# ice40.net
KiCad netlist of a schematic drawn in Altium Designer
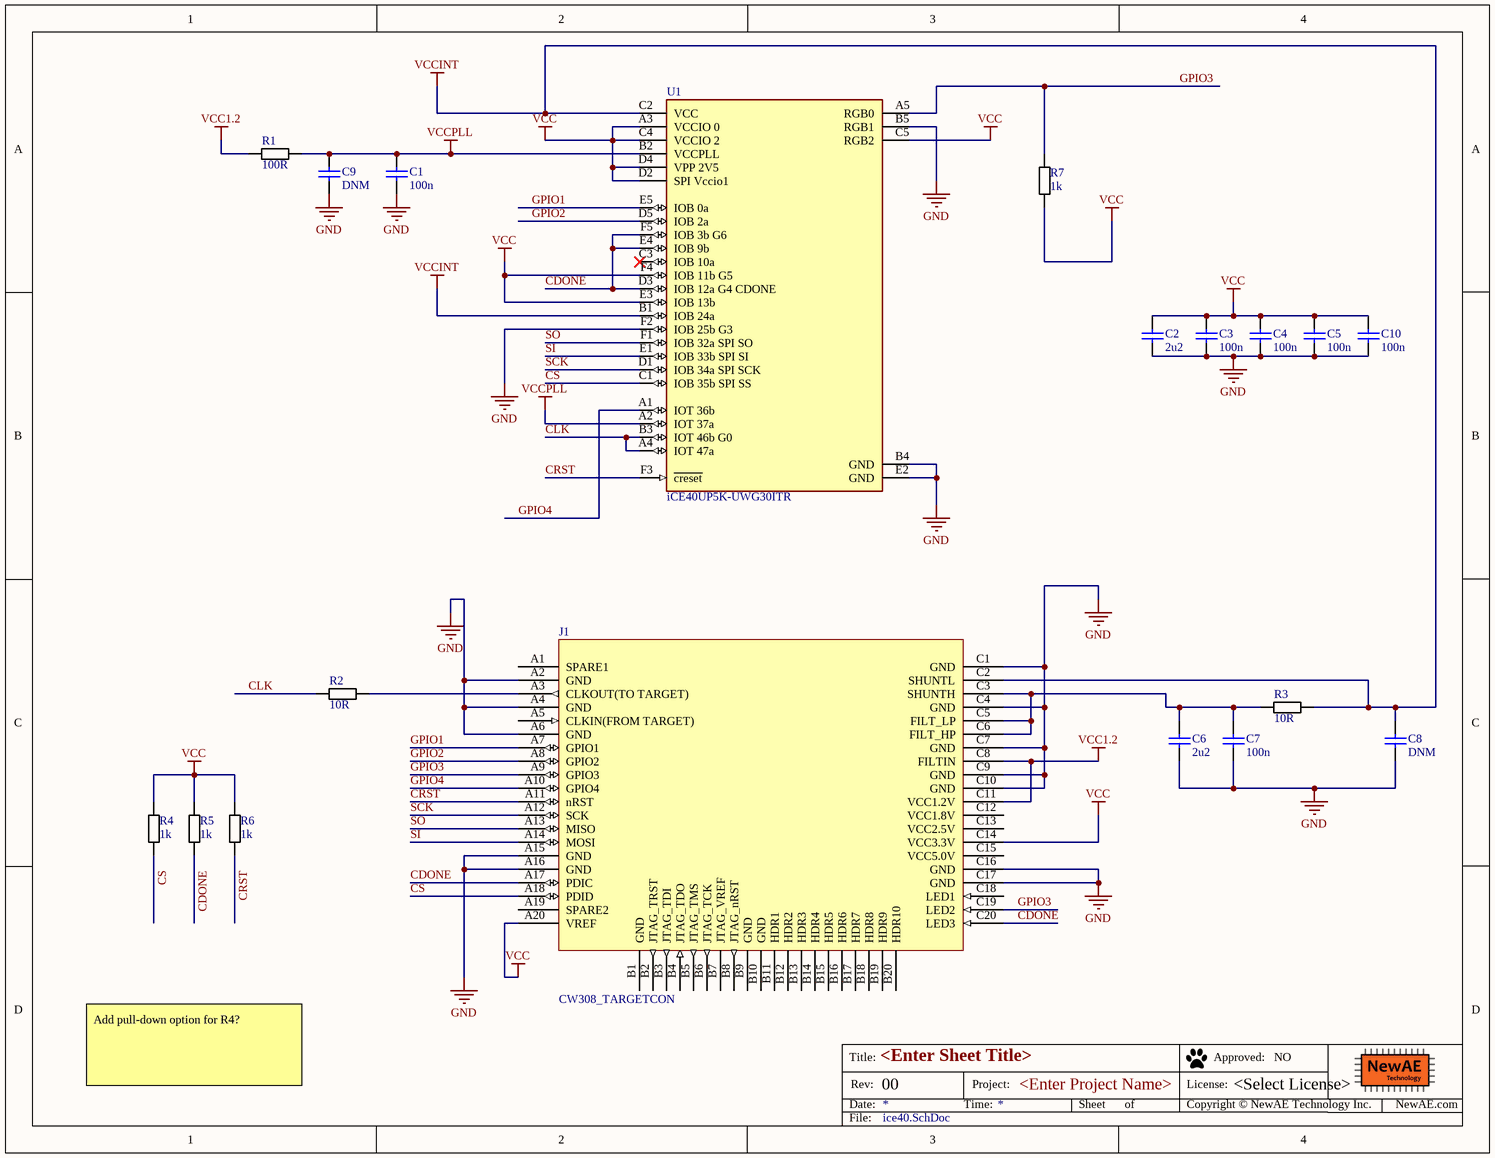
[diagram p0: ice40.SchDoc]

(export (version "E")
  (design (tool "Eeschema 10.0.6"))
  (components
    (comp (ref "C1")
      (value "100n")
      (footprint "CAPC0603_M")
      (description "100n, 0603")
      (fields (field (name "PART NUMBER") "CCHIP-100n-0603"))
      (libsource (lib "NewAE_AltiumLib") (part "CAP"))
    )
    (comp (ref "C2")
      (value "2u2")
      (footprint "CAPC0603_M")
      (description "2u2, 0603")
      (fields (field (name "PART NUMBER") "CCHIP-2u2-0603"))
      (libsource (lib "NewAE_AltiumLib") (part "CAP"))
    )
    (comp (ref "C3")
      (value "100n")
      (footprint "CAPC0603_M")
      (description "100n, 0603")
      (fields (field (name "PART NUMBER") "CCHIP-100n-0603"))
      (libsource (lib "NewAE_AltiumLib") (part "CAP"))
    )
    (comp (ref "C4")
      (value "100n")
      (footprint "CAPC0603_M")
      (description "100n, 0603")
      (fields (field (name "PART NUMBER") "CCHIP-100n-0603"))
      (libsource (lib "NewAE_AltiumLib") (part "CAP"))
    )
    (comp (ref "C5")
      (value "100n")
      (footprint "CAPC0603_M")
      (description "100n, 0603")
      (fields (field (name "PART NUMBER") "CCHIP-100n-0603"))
      (libsource (lib "NewAE_AltiumLib") (part "CAP"))
    )
    (comp (ref "C6")
      (value "2u2")
      (footprint "CAPC0603_M")
      (description "2u2, 0603")
      (fields (field (name "PART NUMBER") "CCHIP-2u2-0603"))
      (libsource (lib "NewAE_AltiumLib") (part "CAP"))
    )
    (comp (ref "C7")
      (value "100n")
      (footprint "CAPC0603_M")
      (description "100n, 0603")
      (fields (field (name "PART NUMBER") "CCHIP-100n-0603"))
      (libsource (lib "NewAE_AltiumLib") (part "CAP"))
    )
    (comp (ref "C8")
      (value "DNM")
      (footprint "CAPC0603_M")
      (description "DNM, 0603")
      (fields (field (name "PART NUMBER") "CCHIP-DNM-0603"))
      (libsource (lib "NewAE_AltiumLib") (part "CAP"))
    )
    (comp (ref "C9")
      (value "DNM")
      (footprint "CAPC0603_M")
      (description "DNM, 0603")
      (fields (field (name "PART NUMBER") "CCHIP-DNM-0603"))
      (libsource (lib "NewAE_AltiumLib") (part "CAP"))
    )
    (comp (ref "C10")
      (value "100n")
      (footprint "CAPC0603_M")
      (description "100n, 0603")
      (fields (field (name "PART NUMBER") "CCHIP-100n-0603"))
      (libsource (lib "NewAE_AltiumLib") (part "CAP"))
    )
    (comp (ref "J1")
      (value "CW308_TARGETCON")
      (footprint "CW308_TBOARD_CONN")
      (description "CW308 \"Standard\" Target Board Connector")
      (fields (field (name "PART NUMBER") "CW308_TBOARD"))
      (libsource (lib "NewAE_AltiumLib") (part "CW308_TBOARD"))
    )
    (comp (ref "R1")
      (value "100R")
      (footprint "RESC1608X55N")
      (description "100R res, 0603, 1%, 1/10W")
      (fields (field (name "PART NUMBER") "RCHIP-100R-0603") (field (name "TOLERANCE") "1%"))
      (libsource (lib "NewAE_AltiumLib") (part "RES-EU"))
    )
    (comp (ref "R2")
      (value "10R")
      (footprint "RESC1608X55N")
      (description "10R res, 0603, 1%, 1/10W")
      (fields (field (name "PART NUMBER") "RCHIP-10R-0603") (field (name "TOLERANCE") "1%"))
      (libsource (lib "NewAE_AltiumLib") (part "RES-EU"))
    )
    (comp (ref "R3")
      (value "10R")
      (footprint "RESC1608X55N")
      (description "10R res, 0603, 1%, 1/10W")
      (fields (field (name "PART NUMBER") "RCHIP-10R-0603") (field (name "TOLERANCE") "1%"))
      (libsource (lib "NewAE_AltiumLib") (part "RES-EU"))
    )
    (comp (ref "R4")
      (value "1k")
      (footprint "RESC1608X55N")
      (description "1k res, 0603, 1%, 1/10W")
      (fields (field (name "PART NUMBER") "RCHIP-1K-0603") (field (name "TOLERANCE") "1%"))
      (libsource (lib "") (part "RES-EU_1"))
    )
    (comp (ref "R5")
      (value "1k")
      (footprint "RESC1608X55N")
      (description "1k res, 0603, 1%, 1/10W")
      (fields (field (name "PART NUMBER") "RCHIP-1K-0603") (field (name "TOLERANCE") "1%"))
      (libsource (lib "") (part "RES-EU_1"))
    )
    (comp (ref "R6")
      (value "1k")
      (footprint "RESC1608X55N")
      (description "1k res, 0603, 1%, 1/10W")
      (fields (field (name "PART NUMBER") "RCHIP-1K-0603") (field (name "TOLERANCE") "1%"))
      (libsource (lib "") (part "RES-EU_1"))
    )
    (comp (ref "R7")
      (value "1k")
      (footprint "RESC1608X55N")
      (description "1k res, 0603, 1%, 1/10W")
      (fields (field (name "PART NUMBER") "RCHIP-1K-0603") (field (name "TOLERANCE") "1%"))
      (libsource (lib "") (part "RES-EU_1"))
    )
    (comp (ref "U1")
      (value "iCE40UP5K-UWG30ITR")
      (footprint "FP-WLSC-30-MFG")
      (description "CE40-ULTRAPLUS, 5280 LUTS, 1.2V")
      (fields
        (field (name "OCTOPART") "https://octopart.com/ice40up5k-uwg30itr-lattice+semiconductor-75367085")
        (field (name "MANUFACTURER") "Lattice Semiconductor")
      )
      (libsource (lib "Altium Content Vault") (part "3413680a180c2a639ae4d36ae520900"))
    )
  )
  (nets
    (net (code "1") (name "/CDONE") (class "Default")
      (node (ref "J1") (pin "A17") (pinfunction "PDIC_A17") (pintype "bidirectional"))
      (node (ref "J1") (pin "C20") (pinfunction "LED3_C20") (pintype "input"))
      (node (ref "R5") (pin "2") (pinfunction "2_2") (pintype "passive"))
      (node (ref "U1") (pin "D3") (pinfunction "IOB_12a_G4_CDONE_D3") (pintype "bidirectional"))
      (node (ref "U1") (pin "E4") (pinfunction "IOB_9b_E4") (pintype "bidirectional"))
      (node (ref "U1") (pin "F5") (pinfunction "IOB_3b_G6_F5") (pintype "bidirectional"))
    )
    (net (code "2") (name "/CLK") (class "Default")
      (node (ref "R2") (pin "1") (pinfunction "1_1") (pintype "passive"))
      (node (ref "U1") (pin "A4") (pinfunction "IOT_47a_A4") (pintype "bidirectional"))
      (node (ref "U1") (pin "B3") (pinfunction "IOT_46b_G0_B3") (pintype "bidirectional"))
    )
    (net (code "3") (name "/CRST") (class "Default")
      (node (ref "J1") (pin "A11") (pinfunction "nRST_A11") (pintype "bidirectional"))
      (node (ref "R6") (pin "2") (pinfunction "2_2") (pintype "passive"))
      (node (ref "U1") (pin "F3") (pinfunction "~{creset}_F3") (pintype "input"))
    )
    (net (code "4") (name "/CS") (class "Default")
      (node (ref "J1") (pin "A18") (pinfunction "PDID_A18") (pintype "bidirectional"))
      (node (ref "R4") (pin "2") (pinfunction "2_2") (pintype "passive"))
      (node (ref "U1") (pin "C1") (pinfunction "IOB_35b_SPI_SS_C1") (pintype "bidirectional"))
    )
    (net (code "5") (name "/GPIO1") (class "Default")
      (node (ref "J1") (pin "A7") (pinfunction "GPIO1_A7") (pintype "bidirectional"))
      (node (ref "U1") (pin "E5") (pinfunction "IOB_0a_E5") (pintype "bidirectional"))
    )
    (net (code "6") (name "/GPIO2") (class "Default")
      (node (ref "J1") (pin "A8") (pinfunction "GPIO2_A8") (pintype "bidirectional"))
      (node (ref "U1") (pin "D5") (pinfunction "IOB_2a_D5") (pintype "bidirectional"))
    )
    (net (code "7") (name "/GPIO3") (class "Default")
      (node (ref "J1") (pin "A9") (pinfunction "GPIO3_A9") (pintype "bidirectional"))
      (node (ref "J1") (pin "C19") (pinfunction "LED2_C19") (pintype "input"))
      (node (ref "R7") (pin "1") (pinfunction "1_1") (pintype "passive"))
      (node (ref "U1") (pin "A5") (pinfunction "RGB0_A5") (pintype "open_collector"))
    )
    (net (code "8") (name "/GPIO4") (class "Default")
      (node (ref "J1") (pin "A10") (pinfunction "GPIO4_A10") (pintype "bidirectional"))
      (node (ref "U1") (pin "A1") (pinfunction "IOT_36b_A1") (pintype "bidirectional"))
    )
    (net (code "9") (name "/SCK") (class "Default")
      (node (ref "J1") (pin "A12") (pinfunction "SCK_A12") (pintype "bidirectional"))
      (node (ref "U1") (pin "D1") (pinfunction "IOB_34a_SPI_SCK_D1") (pintype "bidirectional"))
    )
    (net (code "10") (name "/SI") (class "Default")
      (node (ref "J1") (pin "A14") (pinfunction "MOSI_A14") (pintype "bidirectional"))
      (node (ref "U1") (pin "E1") (pinfunction "IOB_33b_SPI_SI_E1") (pintype "bidirectional"))
    )
    (net (code "11") (name "/SO") (class "Default")
      (node (ref "J1") (pin "A13") (pinfunction "MISO_A13") (pintype "bidirectional"))
      (node (ref "U1") (pin "F1") (pinfunction "IOB_32a_SPI_SO_F1") (pintype "bidirectional"))
    )
    (net (code "12") (name "GND") (class "Default")
      (node (ref "C1") (pin "2") (pinfunction "2_2") (pintype "passive"))
      (node (ref "C10") (pin "2") (pinfunction "2_2") (pintype "passive"))
      (node (ref "C2") (pin "2") (pinfunction "2_2") (pintype "passive"))
      (node (ref "C3") (pin "2") (pinfunction "2_2") (pintype "passive"))
      (node (ref "C4") (pin "2") (pinfunction "2_2") (pintype "passive"))
      (node (ref "C5") (pin "2") (pinfunction "2_2") (pintype "passive"))
      (node (ref "C6") (pin "2") (pinfunction "2_2") (pintype "passive"))
      (node (ref "C7") (pin "2") (pinfunction "2_2") (pintype "passive"))
      (node (ref "C8") (pin "2") (pinfunction "2_2") (pintype "passive"))
      (node (ref "C9") (pin "2") (pinfunction "2_2") (pintype "passive"))
      (node (ref "J1") (pin "A15") (pinfunction "GND_A15") (pintype "passive"))
      (node (ref "J1") (pin "A16") (pinfunction "GND_A16") (pintype "passive"))
      (node (ref "J1") (pin "A2") (pinfunction "GND_A2") (pintype "passive"))
      (node (ref "J1") (pin "A4") (pinfunction "GND_A4") (pintype "passive"))
      (node (ref "J1") (pin "A6") (pinfunction "GND_A6") (pintype "power_in"))
      (node (ref "J1") (pin "C1") (pinfunction "GND_C1") (pintype "power_in"))
      (node (ref "J1") (pin "C10") (pinfunction "GND_C10") (pintype "power_in"))
      (node (ref "J1") (pin "C16") (pinfunction "GND_C16") (pintype "power_in"))
      (node (ref "J1") (pin "C17") (pinfunction "GND_C17") (pintype "power_in"))
      (node (ref "J1") (pin "C4") (pinfunction "GND_C4") (pintype "power_in"))
      (node (ref "J1") (pin "C7") (pinfunction "GND_C7") (pintype "power_in"))
      (node (ref "J1") (pin "C9") (pinfunction "GND_C9") (pintype "power_in"))
      (node (ref "U1") (pin "B4") (pinfunction "GND_B4") (pintype "power_in"))
      (node (ref "U1") (pin "B5") (pinfunction "RGB1_B5") (pintype "open_collector"))
      (node (ref "U1") (pin "E2") (pinfunction "GND_E2") (pintype "power_in"))
      (node (ref "U1") (pin "F2") (pinfunction "IOB_25b_G3_F2") (pintype "bidirectional"))
    )
    (net (code "13") (name "Net-(J1-CLKOUT(TO_TARGET))") (class "Default")
      (node (ref "J1") (pin "A3") (pinfunction "CLKOUT(TO_TARGET)_A3") (pintype "output"))
      (node (ref "R2") (pin "2") (pinfunction "2_2") (pintype "passive"))
    )
    (net (code "14") (name "Net-(J1-FILT_HP)") (class "Default")
      (node (ref "C6") (pin "1") (pinfunction "1_1") (pintype "passive"))
      (node (ref "C7") (pin "1") (pinfunction "1_1") (pintype "passive"))
      (node (ref "J1") (pin "C3") (pinfunction "SHUNTH_C3") (pintype "passive"))
      (node (ref "J1") (pin "C5") (pinfunction "FILT_LP_C5") (pintype "passive"))
      (node (ref "J1") (pin "C6") (pinfunction "FILT_HP_C6") (pintype "passive"))
      (node (ref "R3") (pin "1") (pinfunction "1_1") (pintype "passive"))
    )
    (net (code "15") (name "VCC") (class "Default")
      (node (ref "C10") (pin "1") (pinfunction "1_1") (pintype "passive"))
      (node (ref "C2") (pin "1") (pinfunction "1_1") (pintype "passive"))
      (node (ref "C3") (pin "1") (pinfunction "1_1") (pintype "passive"))
      (node (ref "C4") (pin "1") (pinfunction "1_1") (pintype "passive"))
      (node (ref "C5") (pin "1") (pinfunction "1_1") (pintype "passive"))
      (node (ref "J1") (pin "A20") (pinfunction "VREF_A20") (pintype "tri_state"))
      (node (ref "J1") (pin "C14") (pinfunction "VCC3.3V_C14") (pintype "power_in"))
      (node (ref "R4") (pin "1") (pinfunction "1_1") (pintype "passive"))
      (node (ref "R5") (pin "1") (pinfunction "1_1") (pintype "passive"))
      (node (ref "R6") (pin "1") (pinfunction "1_1") (pintype "passive"))
      (node (ref "R7") (pin "2") (pinfunction "2_2") (pintype "passive"))
      (node (ref "U1") (pin "A3") (pinfunction "VCCIO_0_A3") (pintype "power_in"))
      (node (ref "U1") (pin "C4") (pinfunction "VCCIO_2_C4") (pintype "power_in"))
      (node (ref "U1") (pin "C5") (pinfunction "RGB2_C5") (pintype "open_collector"))
      (node (ref "U1") (pin "D2") (pinfunction "SPI_Vccio1_D2") (pintype "power_in"))
      (node (ref "U1") (pin "D4") (pinfunction "VPP_2V5_D4") (pintype "power_in"))
      (node (ref "U1") (pin "E3") (pinfunction "IOB_13b_E3") (pintype "bidirectional"))
      (node (ref "U1") (pin "F4") (pinfunction "IOB_11b_G5_F4") (pintype "bidirectional"))
    )
    (net (code "16") (name "VCC1.2") (class "Default")
      (node (ref "J1") (pin "C11") (pinfunction "VCC1.2V_C11") (pintype "power_in"))
      (node (ref "J1") (pin "C8") (pinfunction "FILTIN_C8") (pintype "passive"))
      (node (ref "R1") (pin "1") (pinfunction "1_1") (pintype "passive"))
    )
    (net (code "17") (name "VCCINT") (class "Default")
      (node (ref "C8") (pin "1") (pinfunction "1_1") (pintype "passive"))
      (node (ref "J1") (pin "C2") (pinfunction "SHUNTL_C2") (pintype "passive"))
      (node (ref "R3") (pin "2") (pinfunction "2_2") (pintype "passive"))
      (node (ref "U1") (pin "B1") (pinfunction "IOB_24a_B1") (pintype "bidirectional"))
      (node (ref "U1") (pin "C2") (pinfunction "VCC_C2") (pintype "power_in"))
    )
    (net (code "18") (name "VCCPLL") (class "Default")
      (node (ref "C1") (pin "1") (pinfunction "1_1") (pintype "passive"))
      (node (ref "C9") (pin "1") (pinfunction "1_1") (pintype "passive"))
      (node (ref "R1") (pin "2") (pinfunction "2_2") (pintype "passive"))
      (node (ref "U1") (pin "A2") (pinfunction "IOT_37a_A2") (pintype "bidirectional"))
      (node (ref "U1") (pin "B2") (pinfunction "VCCPLL_B2") (pintype "power_in"))
    )
    (net (code "19") (name "unconnected-(J1-CLKIN(FROM_TARGET)-PadA5)") (class "Default")
      (node (ref "J1") (pin "A5") (pinfunction "CLKIN(FROM_TARGET)_A5") (pintype "input"))
    )
    (net (code "20") (name "unconnected-(J1-GND-PadB1)") (class "Default")
      (node (ref "J1") (pin "B1") (pinfunction "GND_B1") (pintype "passive"))
    )
    (net (code "21") (name "unconnected-(J1-GND-PadB9)") (class "Default")
      (node (ref "J1") (pin "B9") (pinfunction "GND_B9") (pintype "passive"))
    )
    (net (code "22") (name "unconnected-(J1-GND-PadB10)") (class "Default")
      (node (ref "J1") (pin "B10") (pinfunction "GND_B10") (pintype "passive"))
    )
    (net (code "23") (name "unconnected-(J1-HDR1-PadB11)") (class "Default")
      (node (ref "J1") (pin "B11") (pinfunction "HDR1_B11") (pintype "passive"))
    )
    (net (code "24") (name "unconnected-(J1-HDR2-PadB12)") (class "Default")
      (node (ref "J1") (pin "B12") (pinfunction "HDR2_B12") (pintype "passive"))
    )
    (net (code "25") (name "unconnected-(J1-HDR3-PadB13)") (class "Default")
      (node (ref "J1") (pin "B13") (pinfunction "HDR3_B13") (pintype "passive"))
    )
    (net (code "26") (name "unconnected-(J1-HDR4-PadB14)") (class "Default")
      (node (ref "J1") (pin "B14") (pinfunction "HDR4_B14") (pintype "passive"))
    )
    (net (code "27") (name "unconnected-(J1-HDR5-PadB15)") (class "Default")
      (node (ref "J1") (pin "B15") (pinfunction "HDR5_B15") (pintype "passive"))
    )
    (net (code "28") (name "unconnected-(J1-HDR6-PadB16)") (class "Default")
      (node (ref "J1") (pin "B16") (pinfunction "HDR6_B16") (pintype "passive"))
    )
    (net (code "29") (name "unconnected-(J1-HDR7-PadB17)") (class "Default")
      (node (ref "J1") (pin "B17") (pinfunction "HDR7_B17") (pintype "passive"))
    )
    (net (code "30") (name "unconnected-(J1-HDR8-PadB18)") (class "Default")
      (node (ref "J1") (pin "B18") (pinfunction "HDR8_B18") (pintype "passive"))
    )
    (net (code "31") (name "unconnected-(J1-HDR9-PadB19)") (class "Default")
      (node (ref "J1") (pin "B19") (pinfunction "HDR9_B19") (pintype "passive"))
    )
    (net (code "32") (name "unconnected-(J1-HDR10-PadB20)") (class "Default")
      (node (ref "J1") (pin "B20") (pinfunction "HDR10_B20") (pintype "passive"))
    )
    (net (code "33") (name "unconnected-(J1-JTAG_TCK-PadB6)") (class "Default")
      (node (ref "J1") (pin "B6") (pinfunction "JTAG_TCK_B6") (pintype "output"))
    )
    (net (code "34") (name "unconnected-(J1-JTAG_TDI-PadB3)") (class "Default")
      (node (ref "J1") (pin "B3") (pinfunction "JTAG_TDI_B3") (pintype "output"))
    )
    (net (code "35") (name "unconnected-(J1-JTAG_TDO-PadB4)") (class "Default")
      (node (ref "J1") (pin "B4") (pinfunction "JTAG_TDO_B4") (pintype "input"))
    )
    (net (code "36") (name "unconnected-(J1-JTAG_TMS-PadB5)") (class "Default")
      (node (ref "J1") (pin "B5") (pinfunction "JTAG_TMS_B5") (pintype "output"))
    )
    (net (code "37") (name "unconnected-(J1-JTAG_TRST-PadB2)") (class "Default")
      (node (ref "J1") (pin "B2") (pinfunction "JTAG_TRST_B2") (pintype "output"))
    )
    (net (code "38") (name "unconnected-(J1-JTAG_VREF-PadB7)") (class "Default")
      (node (ref "J1") (pin "B7") (pinfunction "JTAG_VREF_B7") (pintype "tri_state"))
    )
    (net (code "39") (name "unconnected-(J1-JTAG_nRST-PadB8)") (class "Default")
      (node (ref "J1") (pin "B8") (pinfunction "JTAG_nRST_B8") (pintype "output"))
    )
    (net (code "40") (name "unconnected-(J1-LED1-PadC18)") (class "Default")
      (node (ref "J1") (pin "C18") (pinfunction "LED1_C18") (pintype "input"))
    )
    (net (code "41") (name "unconnected-(J1-SPARE1-PadA1)") (class "Default")
      (node (ref "J1") (pin "A1") (pinfunction "SPARE1_A1") (pintype "passive"))
    )
    (net (code "42") (name "unconnected-(J1-SPARE2-PadA19)") (class "Default")
      (node (ref "J1") (pin "A19") (pinfunction "SPARE2_A19") (pintype "passive"))
    )
    (net (code "43") (name "unconnected-(J1-VCC1.8V-PadC12)") (class "Default")
      (node (ref "J1") (pin "C12") (pinfunction "VCC1.8V_C12") (pintype "power_in"))
    )
    (net (code "44") (name "unconnected-(J1-VCC2.5V-PadC13)") (class "Default")
      (node (ref "J1") (pin "C13") (pinfunction "VCC2.5V_C13") (pintype "power_in"))
    )
    (net (code "45") (name "unconnected-(J1-VCC5.0V-PadC15)") (class "Default")
      (node (ref "J1") (pin "C15") (pinfunction "VCC5.0V_C15") (pintype "power_in"))
    )
    (net (code "46") (name "unconnected-(U1-IOB_10a-PadC3)") (class "Default")
      (node (ref "U1") (pin "C3") (pinfunction "IOB_10a_C3") (pintype "bidirectional+no_connect"))
    )
  )
)
